# lv_1.net
KiCad netlist of a schematic drawn in Altium Designer
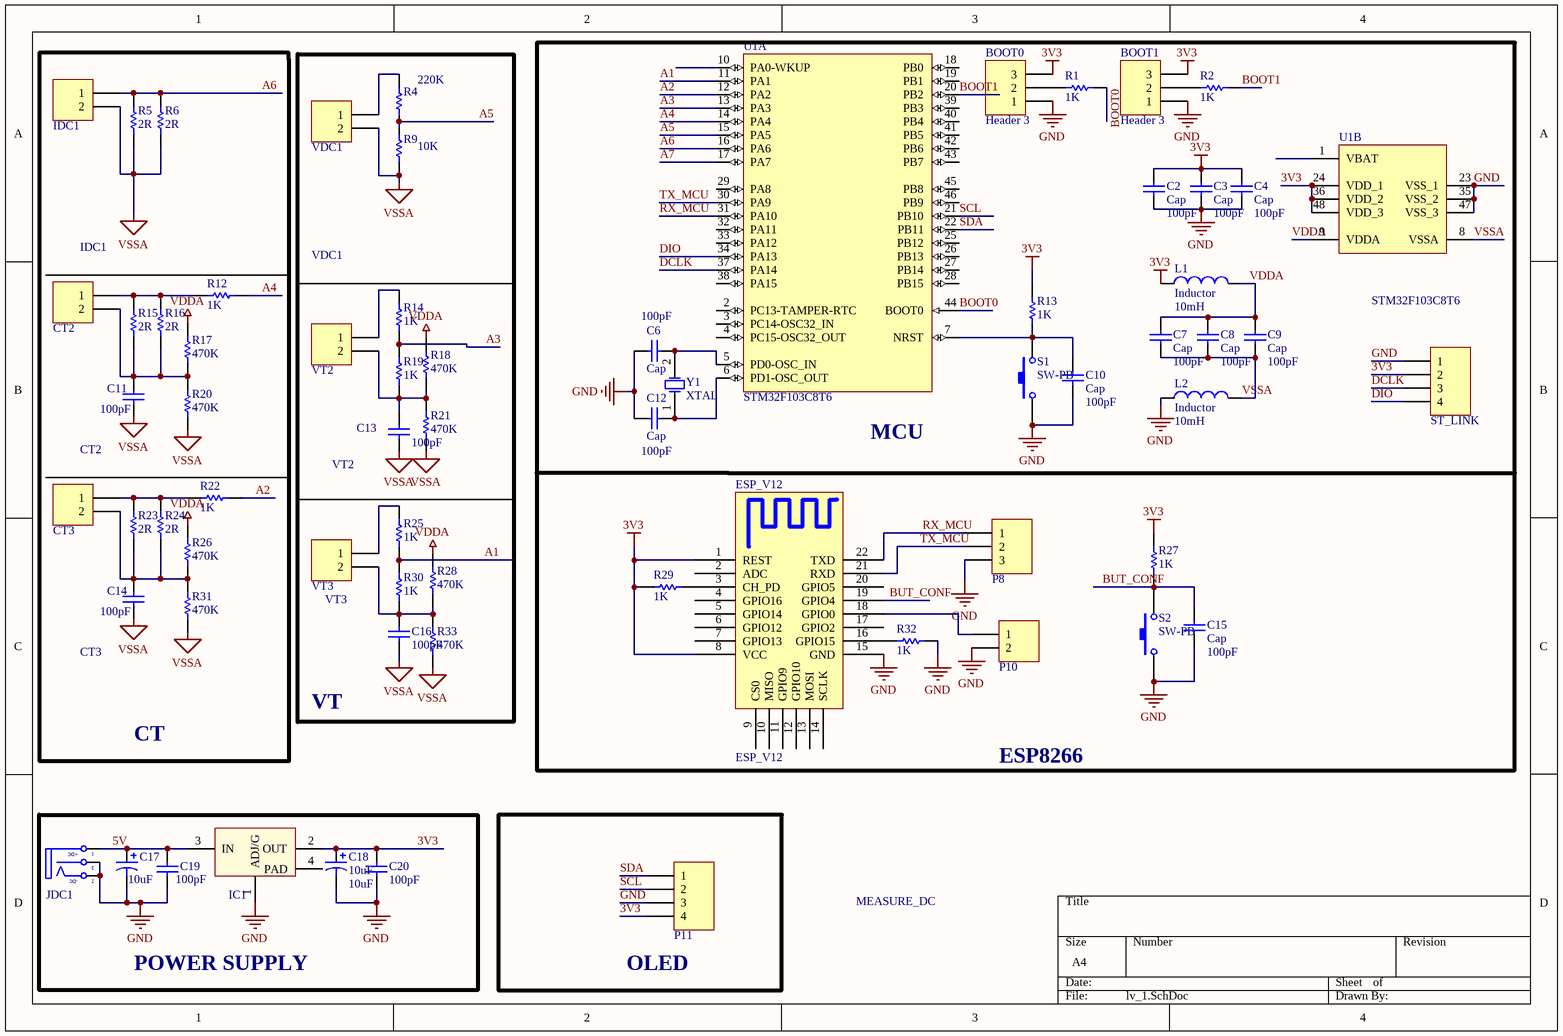
[diagram p0: lv_1.SchDoc]

(export (version "E")
  (design (tool "Eeschema 10.0.6"))
  (components
    (comp (ref "BOOT0")
      (value "Header 3")
      (footprint "JP3")
      (description "Header, 3-Pin")
      (fields (field (name "PUBLISHER") "Altium Limited"))
      (libsource (lib "Miscellaneous Connectors") (part "Header 3"))
    )
    (comp (ref "BOOT1")
      (value "Header 3")
      (footprint "JP3")
      (description "Header, 3-Pin")
      (fields (field (name "PUBLISHER") "Altium Limited"))
      (libsource (lib "Miscellaneous Connectors") (part "Header 3"))
    )
    (comp (ref "C2")
      (value "Cap")
      (footprint "CAP-SM-0603")
      (description "Capacitor")
      (fields (field (name "ALTIUM_VALUE") "100pF") (field (name "PUBLISHER") "Altium Limited"))
      (libsource (lib "Miscellaneous Devices") (part "Cap"))
    )
    (comp (ref "C3")
      (value "Cap")
      (footprint "CAP-SM-0603")
      (description "Capacitor")
      (fields (field (name "ALTIUM_VALUE") "100pF") (field (name "PUBLISHER") "Altium Limited"))
      (libsource (lib "Miscellaneous Devices") (part "Cap"))
    )
    (comp (ref "C4")
      (value "Cap")
      (footprint "CAP-SM-0603")
      (description "Capacitor")
      (fields (field (name "ALTIUM_VALUE") "100pF") (field (name "PUBLISHER") "Altium Limited"))
      (libsource (lib "Miscellaneous Devices") (part "Cap"))
    )
    (comp (ref "C6")
      (value "Cap")
      (footprint "CAP-SM-0603")
      (description "Capacitor")
      (fields (field (name "ALTIUM_VALUE") "100pF") (field (name "PUBLISHER") "Altium Limited"))
      (libsource (lib "Miscellaneous Devices") (part "Cap"))
    )
    (comp (ref "C7")
      (value "Cap")
      (footprint "CAP-SM-0603")
      (description "Capacitor")
      (fields (field (name "ALTIUM_VALUE") "100pF") (field (name "PUBLISHER") "Altium Limited"))
      (libsource (lib "Miscellaneous Devices") (part "Cap"))
    )
    (comp (ref "C8")
      (value "Cap")
      (footprint "CAP-SM-0603")
      (description "Capacitor")
      (fields (field (name "ALTIUM_VALUE") "100pF") (field (name "PUBLISHER") "Altium Limited"))
      (libsource (lib "Miscellaneous Devices") (part "Cap"))
    )
    (comp (ref "C9")
      (value "Cap")
      (footprint "CAP-SM-0603")
      (description "Capacitor")
      (fields (field (name "ALTIUM_VALUE") "100pF") (field (name "PUBLISHER") "Altium Limited"))
      (libsource (lib "Miscellaneous Devices") (part "Cap"))
    )
    (comp (ref "C10")
      (value "Cap")
      (footprint "CAP-SM-0603")
      (description "Capacitor")
      (fields (field (name "ALTIUM_VALUE") "100pF") (field (name "PUBLISHER") "Altium Limited"))
      (libsource (lib "Miscellaneous Devices") (part "Cap"))
    )
    (comp (ref "C11")
      (value "100pF")
      (footprint "CAP-SM-0603")
      (description "Capacitor")
      (fields (field (name "Comment") "Cap Non-Pol SMD"))
      (libsource (lib "PIF_Library") (part "Cap Non-Pol SMD"))
    )
    (comp (ref "C12")
      (value "Cap")
      (footprint "CAP-SM-0603")
      (description "Capacitor")
      (fields (field (name "ALTIUM_VALUE") "100pF") (field (name "PUBLISHER") "Altium Limited"))
      (libsource (lib "Miscellaneous Devices") (part "Cap"))
    )
    (comp (ref "C13")
      (value "100pF")
      (footprint "CAP-SM-0603")
      (description "Capacitor")
      (fields (field (name "Comment") "Cap Non-Pol SMD"))
      (libsource (lib "PIF_Library") (part "Cap Non-Pol SMD"))
    )
    (comp (ref "C14")
      (value "100pF")
      (footprint "CAP-SM-0603")
      (description "Capacitor")
      (fields (field (name "Comment") "Cap Non-Pol SMD"))
      (libsource (lib "PIF_Library") (part "Cap Non-Pol SMD"))
    )
    (comp (ref "C15")
      (value "Cap")
      (footprint "CAP-SM-0603")
      (description "Capacitor")
      (fields (field (name "ALTIUM_VALUE") "100pF") (field (name "PUBLISHER") "Altium Limited"))
      (libsource (lib "Miscellaneous Devices") (part "Cap"))
    )
    (comp (ref "C16")
      (value "100pF")
      (footprint "CAP-SM-0603")
      (description "Capacitor")
      (fields (field (name "Comment") "Cap Non-Pol SMD"))
      (libsource (lib "PIF_Library") (part "Cap Non-Pol SMD"))
    )
    (comp (ref "C17")
      (value "10uF")
      (footprint "CP1/2")
      (description "Polarized Capacitor (Radial)")
      (fields (field (name "PUBLISHER") "Altium Limited"))
      (libsource (lib "Miscellaneous Devices") (part "Cap Pol1"))
    )
    (comp (ref "C18")
      (value "10uF")
      (footprint "CP1/2")
      (description "Polarized Capacitor (Radial)")
      (fields (field (name "ALTIUM_VALUE") "10uF") (field (name "PUBLISHER") "Altium Limited"))
      (libsource (lib "Miscellaneous Devices") (part "Cap Pol1"))
    )
    (comp (ref "C19")
      (value "100pF")
      (footprint "CAP-SM-0603")
      (description "Capacitor")
      (fields (field (name "Comment") "Cap Non-Pol SMD"))
      (libsource (lib "PIF_Library") (part "Cap Non-Pol SMD"))
    )
    (comp (ref "C20")
      (value "100pF")
      (footprint "CAP-SM-0603")
      (description "Capacitor")
      (fields (field (name "Comment") "Cap Non-Pol SMD"))
      (libsource (lib "PIF_Library") (part "Cap Non-Pol SMD"))
    )
    (comp (ref "CT2")
      (value "Domino 2")
      (footprint "DOMINO 2- 5mm")
      (description "Domino, 2-Pin")
      (fields (field (name "PUBLISHER") "Altium Limited"))
      (libsource (lib "PIF_Library") (part "Domino 2"))
    )
    (comp (ref "CT3")
      (value "Domino 2")
      (footprint "DOMINO 2- 5mm")
      (description "Domino, 2-Pin")
      (fields (field (name "PUBLISHER") "Altium Limited"))
      (libsource (lib "PIF_Library") (part "Domino 2"))
    )
    (comp (ref "ESP_V12")
      (value "ESP_V12")
      (footprint "ESP_12_E")
      (libsource (lib "espv12") (part "Component_1"))
    )
    (comp (ref "IC1")
      (value "LM1117")
      (footprint "SOT223-4N")
      (description "Available in 1.8V, 2.5V, 2.85V, 3.3V, 5V, and  Adjustable Versions")
      (libsource (lib "PIF_Library") (part "LM1117"))
    )
    (comp (ref "IDC1")
      (value "Domino 2")
      (footprint "DOMINO 2- 5mm")
      (description "Domino, 2-Pin")
      (fields (field (name "PUBLISHER") "Altium Limited"))
      (libsource (lib "PIF_Library") (part "Domino 2"))
    )
    (comp (ref "JDC1")
      (value "Jack DC")
      (footprint "DC-IN")
      (description "Jack DC input")
      (libsource (lib "PIF_Library") (part "Jack DC"))
    )
    (comp (ref "L1")
      (value "Inductor")
      (footprint "CAP-SM-0603")
      (fields (field (name "ALTIUM_VALUE") "10mH") (field (name "PUBLISHER") "Altium Limited"))
      (libsource (lib "Miscellaneous Devices") (part "Inductor"))
    )
    (comp (ref "L2")
      (value "Inductor")
      (footprint "CAP-SM-0603")
      (fields (field (name "ALTIUM_VALUE") "10mH") (field (name "PUBLISHER") "Altium Limited"))
      (libsource (lib "Miscellaneous Devices") (part "Inductor"))
    )
    (comp (ref "P8")
      (value "Header 3")
      (footprint "JP3")
      (description "Header, 3-Pin")
      (fields (field (name "PUBLISHER") "Altium Limited"))
      (libsource (lib "PIF_Library") (part "Header 3"))
    )
    (comp (ref "P10")
      (value "Header 2")
      (footprint "JP2")
      (description "Header, 2-Pin")
      (fields (field (name "PUBLISHER") "Altium Limited"))
      (libsource (lib "PIF_Library") (part "Header 2"))
    )
    (comp (ref "P11")
      (value "Header 4")
      (footprint "JP4")
      (description "Header, 4-Pin")
      (fields (field (name "PUBLISHER") "Altium Limited"))
      (libsource (lib "PIF_Library") (part "Header 4"))
    )
    (comp (ref "R1")
      (value "1K")
      (footprint "RES-SM-0603")
      (description "Resistor")
      (fields (field (name "Comment") "RESISTOR SMD"))
      (libsource (lib "PIF_Library") (part "RESISTOR SMD"))
    )
    (comp (ref "R2")
      (value "1K")
      (footprint "RES-SM-0603")
      (description "Resistor")
      (fields (field (name "Comment") "RESISTOR SMD"))
      (libsource (lib "PIF_Library") (part "RESISTOR SMD"))
    )
    (comp (ref "R4")
      (value "220K")
      (footprint "RES-SM-0603")
      (description "Resistor")
      (libsource (lib "PIF_Library") (part "RESISTOR SMD"))
    )
    (comp (ref "R5")
      (value "2R")
      (footprint "RES-SM-0603")
      (description "Resistor")
      (fields (field (name "Comment") "RESISTOR SMD"))
      (libsource (lib "PIF_Library") (part "RESISTOR SMD"))
    )
    (comp (ref "R6")
      (value "2R")
      (footprint "RES-SM-0603")
      (description "Resistor")
      (fields (field (name "Comment") "RESISTOR SMD"))
      (libsource (lib "PIF_Library") (part "RESISTOR SMD"))
    )
    (comp (ref "R9")
      (value "10K")
      (footprint "RES-SM-0603")
      (description "Resistor")
      (libsource (lib "PIF_Library") (part "RESISTOR SMD"))
    )
    (comp (ref "R12")
      (value "1K")
      (footprint "RES-SM-0603")
      (description "Resistor")
      (fields (field (name "Comment") "RESISTOR SMD"))
      (libsource (lib "PIF_Library") (part "RESISTOR SMD"))
    )
    (comp (ref "R13")
      (value "1K")
      (footprint "RES-SM-0603")
      (description "Resistor")
      (fields (field (name "Comment") "RESISTOR SMD"))
      (libsource (lib "PIF_Library") (part "RESISTOR SMD"))
    )
    (comp (ref "R14")
      (value "1K")
      (footprint "RES-SM-0603")
      (description "Resistor")
      (fields (field (name "Comment") "RESISTOR SMD"))
      (libsource (lib "PIF_Library") (part "RESISTOR SMD"))
    )
    (comp (ref "R15")
      (value "2R")
      (footprint "RES-SM-0603")
      (description "Resistor")
      (fields (field (name "Comment") "RESISTOR SMD"))
      (libsource (lib "PIF_Library") (part "RESISTOR SMD"))
    )
    (comp (ref "R16")
      (value "2R")
      (footprint "RES-SM-0603")
      (description "Resistor")
      (fields (field (name "Comment") "RESISTOR SMD"))
      (libsource (lib "PIF_Library") (part "RESISTOR SMD"))
    )
    (comp (ref "R17")
      (value "470K")
      (footprint "RES-SM-0603")
      (description "Resistor")
      (fields (field (name "Comment") "RESISTOR SMD"))
      (libsource (lib "PIF_Library") (part "RESISTOR SMD"))
    )
    (comp (ref "R18")
      (value "470K")
      (footprint "RES-SM-0603")
      (description "Resistor")
      (fields (field (name "Comment") "RESISTOR SMD"))
      (libsource (lib "PIF_Library") (part "RESISTOR SMD"))
    )
    (comp (ref "R19")
      (value "1K")
      (footprint "RES-SM-0603")
      (description "Resistor")
      (fields (field (name "Comment") "RESISTOR SMD"))
      (libsource (lib "PIF_Library") (part "RESISTOR SMD"))
    )
    (comp (ref "R20")
      (value "470K")
      (footprint "RES-SM-0603")
      (description "Resistor")
      (fields (field (name "Comment") "RESISTOR SMD"))
      (libsource (lib "PIF_Library") (part "RESISTOR SMD"))
    )
    (comp (ref "R21")
      (value "470K")
      (footprint "RES-SM-0603")
      (description "Resistor")
      (fields (field (name "Comment") "RESISTOR SMD"))
      (libsource (lib "PIF_Library") (part "RESISTOR SMD"))
    )
    (comp (ref "R22")
      (value "1K")
      (footprint "RES-SM-0603")
      (description "Resistor")
      (fields (field (name "Comment") "RESISTOR SMD"))
      (libsource (lib "PIF_Library") (part "RESISTOR SMD"))
    )
    (comp (ref "R23")
      (value "2R")
      (footprint "RES-SM-0603")
      (description "Resistor")
      (fields (field (name "Comment") "RESISTOR SMD"))
      (libsource (lib "PIF_Library") (part "RESISTOR SMD"))
    )
    (comp (ref "R24")
      (value "2R")
      (footprint "RES-SM-0603")
      (description "Resistor")
      (fields (field (name "Comment") "RESISTOR SMD"))
      (libsource (lib "PIF_Library") (part "RESISTOR SMD"))
    )
    (comp (ref "R25")
      (value "1K")
      (footprint "RES-SM-0603")
      (description "Resistor")
      (fields (field (name "Comment") "RESISTOR SMD"))
      (libsource (lib "PIF_Library") (part "RESISTOR SMD"))
    )
    (comp (ref "R26")
      (value "470K")
      (footprint "RES-SM-0603")
      (description "Resistor")
      (fields (field (name "Comment") "RESISTOR SMD"))
      (libsource (lib "PIF_Library") (part "RESISTOR SMD"))
    )
    (comp (ref "R27")
      (value "1K")
      (footprint "RES-SM-0603")
      (description "Resistor")
      (fields (field (name "Comment") "RESISTOR SMD"))
      (libsource (lib "PIF_Library") (part "RESISTOR SMD"))
    )
    (comp (ref "R28")
      (value "470K")
      (footprint "RES-SM-0603")
      (description "Resistor")
      (fields (field (name "Comment") "RESISTOR SMD"))
      (libsource (lib "PIF_Library") (part "RESISTOR SMD"))
    )
    (comp (ref "R29")
      (value "1K")
      (footprint "RES-SM-0603")
      (description "Resistor")
      (fields (field (name "Comment") "RESISTOR SMD"))
      (libsource (lib "PIF_Library") (part "RESISTOR SMD"))
    )
    (comp (ref "R30")
      (value "1K")
      (footprint "RES-SM-0603")
      (description "Resistor")
      (fields (field (name "Comment") "RESISTOR SMD"))
      (libsource (lib "PIF_Library") (part "RESISTOR SMD"))
    )
    (comp (ref "R31")
      (value "470K")
      (footprint "RES-SM-0603")
      (description "Resistor")
      (fields (field (name "Comment") "RESISTOR SMD"))
      (libsource (lib "PIF_Library") (part "RESISTOR SMD"))
    )
    (comp (ref "R32")
      (value "1K")
      (footprint "RES-SM-0603")
      (description "Resistor")
      (fields (field (name "Comment") "RESISTOR SMD"))
      (libsource (lib "PIF_Library") (part "RESISTOR SMD"))
    )
    (comp (ref "R33")
      (value "470K")
      (footprint "RES-SM-0603")
      (description "Resistor")
      (fields (field (name "Comment") "RESISTOR SMD"))
      (libsource (lib "PIF_Library") (part "RESISTOR SMD"))
    )
    (comp (ref "S1")
      (value "SW-PB")
      (footprint "Tact SW 4 pin")
      (description "Switch")
      (fields (field (name "PUBLISHER") "Altium Limited"))
      (libsource (lib "Miscellaneous Devices") (part "SW-PB"))
    )
    (comp (ref "S2")
      (value "SW-PB")
      (footprint "Tact SW 4 pin")
      (description "Switch")
      (fields (field (name "PUBLISHER") "Altium Limited"))
      (libsource (lib "Miscellaneous Devices") (part "SW-PB"))
    )
    (comp (ref "ST_LINK")
      (value "Header 4")
      (footprint "JP4")
      (description "Header, 4-Pin")
      (fields (field (name "PUBLISHER") "Altium Limited"))
      (libsource (lib "PIF_Schematic_Lib") (part "Header 4"))
    )
    (comp (ref "U1")
      (value "STM32F103C8T6")
      (footprint "STM-LQFP48_L")
      (libsource (lib "STMicroelectronics STM32 F1") (part "STM32F103C8T6"))
    )
    (comp (ref "VDC1")
      (value "Domino 2")
      (footprint "DOMINO 2- 5mm")
      (description "Domino, 2-Pin")
      (fields (field (name "PUBLISHER") "Altium Limited"))
      (libsource (lib "PIF_Library") (part "Domino 2"))
    )
    (comp (ref "VT2")
      (value "Domino 2")
      (footprint "DOMINO 2- 5mm")
      (description "Domino, 2-Pin")
      (fields (field (name "PUBLISHER") "Altium Limited"))
      (libsource (lib "PIF_Library") (part "Domino 2"))
    )
    (comp (ref "VT3")
      (value "Domino 2")
      (footprint "DOMINO 2- 5mm")
      (description "Domino, 2-Pin")
      (fields (field (name "PUBLISHER") "Altium Limited"))
      (libsource (lib "PIF_Library") (part "Domino 2"))
    )
    (comp (ref "Y1")
      (value "XTAL")
      (footprint "XT2")
      (description "Crystal Oscillator")
      (fields (field (name "PUBLISHER") "Altium Limited"))
      (libsource (lib "Miscellaneous Devices") (part "XTAL"))
    )
  )
  (nets
    (net (code "1") (name "/5V") (class "Default")
      (node (ref "C17") (pin "1") (pinfunction "1_1") (pintype "passive"))
      (node (ref "C19") (pin "2") (pinfunction "2_2") (pintype "passive"))
      (node (ref "IC1") (pin "3") (pinfunction "IN_3") (pintype "passive"))
      (node (ref "JDC1") (pin "1") (pinfunction "T_1") (pintype "passive"))
    )
    (net (code "2") (name "/A1") (class "Default")
      (node (ref "R25") (pin "1") (pinfunction "1_1") (pintype "passive"))
      (node (ref "R30") (pin "2") (pinfunction "2_2") (pintype "passive"))
      (node (ref "U1") (pin "11") (pinfunction "PA1_11") (pintype "bidirectional"))
    )
    (net (code "3") (name "/A2") (class "Default")
      (node (ref "R22") (pin "1") (pinfunction "1_1") (pintype "passive"))
      (node (ref "U1") (pin "12") (pinfunction "PA2_12") (pintype "bidirectional"))
    )
    (net (code "4") (name "/A3") (class "Default")
      (node (ref "R14") (pin "1") (pinfunction "1_1") (pintype "passive"))
      (node (ref "R19") (pin "2") (pinfunction "2_2") (pintype "passive"))
      (node (ref "U1") (pin "13") (pinfunction "PA3_13") (pintype "bidirectional"))
    )
    (net (code "5") (name "/A4") (class "Default")
      (node (ref "R12") (pin "1") (pinfunction "1_1") (pintype "passive"))
      (node (ref "U1") (pin "14") (pinfunction "PA4_14") (pintype "bidirectional"))
    )
    (net (code "6") (name "/A5") (class "Default")
      (node (ref "R4") (pin "1") (pinfunction "1_1") (pintype "passive"))
      (node (ref "R9") (pin "2") (pinfunction "2_2") (pintype "passive"))
      (node (ref "U1") (pin "15") (pinfunction "PA5_15") (pintype "bidirectional"))
    )
    (net (code "7") (name "/A6") (class "Default")
      (node (ref "IDC1") (pin "1") (pinfunction "1_1") (pintype "passive"))
      (node (ref "R5") (pin "2") (pinfunction "2_2") (pintype "passive"))
      (node (ref "R6") (pin "2") (pinfunction "2_2") (pintype "passive"))
      (node (ref "U1") (pin "16") (pinfunction "PA6_16") (pintype "bidirectional"))
    )
    (net (code "8") (name "/A7") (class "Default")
      (node (ref "U1") (pin "17") (pinfunction "PA7_17") (pintype "bidirectional"))
    )
    (net (code "9") (name "/BOOT0") (class "Default")
      (node (ref "R1") (pin "1") (pinfunction "1_1") (pintype "passive"))
      (node (ref "U1") (pin "44") (pinfunction "BOOT0_44") (pintype "input"))
    )
    (net (code "10") (name "/BOOT1") (class "Default")
      (node (ref "R2") (pin "1") (pinfunction "1_1") (pintype "passive"))
      (node (ref "U1") (pin "20") (pinfunction "PB2_20") (pintype "bidirectional"))
    )
    (net (code "11") (name "/BUT_CONF") (class "Default")
      (node (ref "C15") (pin "2") (pinfunction "2_2") (pintype "passive"))
      (node (ref "ESP_V12") (pin "19") (pinfunction "GPIO4_19") (pintype "passive"))
      (node (ref "R27") (pin "2") (pinfunction "2_2") (pintype "passive"))
      (node (ref "S2") (pin "2") (pinfunction "2_2") (pintype "passive"))
    )
    (net (code "12") (name "/DCLK") (class "Default")
      (node (ref "ST_LINK") (pin "3") (pinfunction "3_3") (pintype "passive"))
      (node (ref "U1") (pin "37") (pinfunction "PA14_37") (pintype "bidirectional"))
    )
    (net (code "13") (name "/DIO") (class "Default")
      (node (ref "ST_LINK") (pin "4") (pinfunction "4_4") (pintype "passive"))
      (node (ref "U1") (pin "34") (pinfunction "PA13_34") (pintype "bidirectional"))
    )
    (net (code "14") (name "/RX_MCU") (class "Default")
      (node (ref "ESP_V12") (pin "22") (pinfunction "TXD_22") (pintype "passive"))
      (node (ref "P8") (pin "1") (pinfunction "1_1") (pintype "passive"))
      (node (ref "U1") (pin "31") (pinfunction "PA10_31") (pintype "bidirectional"))
    )
    (net (code "15") (name "/SCL") (class "Default")
      (node (ref "P11") (pin "2") (pinfunction "2_2") (pintype "passive"))
      (node (ref "U1") (pin "21") (pinfunction "PB10_21") (pintype "bidirectional"))
    )
    (net (code "16") (name "/SDA") (class "Default")
      (node (ref "P11") (pin "1") (pinfunction "1_1") (pintype "passive"))
      (node (ref "U1") (pin "22") (pinfunction "PB11_22") (pintype "bidirectional"))
    )
    (net (code "17") (name "/TX_MCU") (class "Default")
      (node (ref "ESP_V12") (pin "21") (pinfunction "RXD_21") (pintype "passive"))
      (node (ref "P8") (pin "2") (pinfunction "2_2") (pintype "passive"))
      (node (ref "U1") (pin "30") (pinfunction "PA9_30") (pintype "bidirectional"))
    )
    (net (code "18") (name "3V3") (class "Default")
      (node (ref "BOOT0") (pin "3") (pinfunction "3_3") (pintype "passive"))
      (node (ref "BOOT1") (pin "3") (pinfunction "3_3") (pintype "passive"))
      (node (ref "C18") (pin "1") (pinfunction "1_1") (pintype "passive"))
      (node (ref "C2") (pin "2") (pinfunction "2_2") (pintype "passive"))
      (node (ref "C20") (pin "2") (pinfunction "2_2") (pintype "passive"))
      (node (ref "C3") (pin "2") (pinfunction "2_2") (pintype "passive"))
      (node (ref "C4") (pin "2") (pinfunction "2_2") (pintype "passive"))
      (node (ref "ESP_V12") (pin "1") (pinfunction "REST_1") (pintype "passive"))
      (node (ref "ESP_V12") (pin "8") (pinfunction "VCC_8") (pintype "passive"))
      (node (ref "IC1") (pin "2") (pinfunction "OUT_2") (pintype "passive"))
      (node (ref "L1") (pin "1") (pinfunction "1_1") (pintype "passive"))
      (node (ref "P11") (pin "4") (pinfunction "4_4") (pintype "passive"))
      (node (ref "R13") (pin "1") (pinfunction "1_1") (pintype "passive"))
      (node (ref "R27") (pin "1") (pinfunction "1_1") (pintype "passive"))
      (node (ref "R29") (pin "1") (pinfunction "1_1") (pintype "passive"))
      (node (ref "ST_LINK") (pin "2") (pinfunction "2_2") (pintype "passive"))
      (node (ref "U1") (pin "24") (pinfunction "VDD_1_24") (pintype "power_in"))
      (node (ref "U1") (pin "36") (pinfunction "VDD_2_36") (pintype "power_in"))
      (node (ref "U1") (pin "48") (pinfunction "VDD_3_48") (pintype "power_in"))
    )
    (net (code "19") (name "GND") (class "Default")
      (node (ref "BOOT0") (pin "1") (pinfunction "1_1") (pintype "passive"))
      (node (ref "BOOT1") (pin "1") (pinfunction "1_1") (pintype "passive"))
      (node (ref "C10") (pin "1") (pinfunction "1_1") (pintype "passive"))
      (node (ref "C12") (pin "1") (pinfunction "1_1") (pintype "passive"))
      (node (ref "C15") (pin "1") (pinfunction "1_1") (pintype "passive"))
      (node (ref "C17") (pin "2") (pinfunction "2_2") (pintype "passive"))
      (node (ref "C18") (pin "2") (pinfunction "2_2") (pintype "passive"))
      (node (ref "C19") (pin "1") (pinfunction "1_1") (pintype "passive"))
      (node (ref "C2") (pin "1") (pinfunction "1_1") (pintype "passive"))
      (node (ref "C20") (pin "1") (pinfunction "1_1") (pintype "passive"))
      (node (ref "C3") (pin "1") (pinfunction "1_1") (pintype "passive"))
      (node (ref "C4") (pin "1") (pinfunction "1_1") (pintype "passive"))
      (node (ref "C6") (pin "1") (pinfunction "1_1") (pintype "passive"))
      (node (ref "ESP_V12") (pin "15") (pinfunction "GND_15") (pintype "passive"))
      (node (ref "IC1") (pin "1") (pinfunction "ADJ/G_1") (pintype "passive"))
      (node (ref "JDC1") (pin "2") (pinfunction "TN_2") (pintype "passive"))
      (node (ref "JDC1") (pin "3") (pinfunction "S_3") (pintype "power_in"))
      (node (ref "L2") (pin "1") (pinfunction "1_1") (pintype "passive"))
      (node (ref "P10") (pin "2") (pinfunction "2_2") (pintype "passive"))
      (node (ref "P11") (pin "3") (pinfunction "3_3") (pintype "passive"))
      (node (ref "P8") (pin "3") (pinfunction "3_3") (pintype "passive"))
      (node (ref "R32") (pin "2") (pinfunction "2_2") (pintype "passive"))
      (node (ref "S1") (pin "1") (pinfunction "1_1") (pintype "passive"))
      (node (ref "S2") (pin "1") (pinfunction "1_1") (pintype "passive"))
      (node (ref "ST_LINK") (pin "1") (pinfunction "1_1") (pintype "passive"))
      (node (ref "U1") (pin "23") (pinfunction "VSS_1_23") (pintype "power_in"))
      (node (ref "U1") (pin "35") (pinfunction "VSS_2_35") (pintype "power_in"))
      (node (ref "U1") (pin "47") (pinfunction "VSS_3_47") (pintype "power_in"))
    )
    (net (code "20") (name "Net-(BOOT0-Pad2)") (class "Default")
      (node (ref "BOOT0") (pin "2") (pinfunction "2_2") (pintype "passive"))
      (node (ref "R1") (pin "2") (pinfunction "2_2") (pintype "passive"))
    )
    (net (code "21") (name "Net-(BOOT1-Pad2)") (class "Default")
      (node (ref "BOOT1") (pin "2") (pinfunction "2_2") (pintype "passive"))
      (node (ref "R2") (pin "2") (pinfunction "2_2") (pintype "passive"))
    )
    (net (code "22") (name "Net-(C11-Pad2)") (class "Default")
      (node (ref "C11") (pin "2") (pinfunction "2_2") (pintype "passive"))
      (node (ref "CT2") (pin "2") (pinfunction "2_2") (pintype "passive"))
      (node (ref "R15") (pin "1") (pinfunction "1_1") (pintype "passive"))
      (node (ref "R16") (pin "1") (pinfunction "1_1") (pintype "passive"))
      (node (ref "R17") (pin "1") (pinfunction "1_1") (pintype "passive"))
      (node (ref "R20") (pin "2") (pinfunction "2_2") (pintype "passive"))
    )
    (net (code "23") (name "Net-(C13-Pad2)") (class "Default")
      (node (ref "C13") (pin "2") (pinfunction "2_2") (pintype "passive"))
      (node (ref "R18") (pin "1") (pinfunction "1_1") (pintype "passive"))
      (node (ref "R19") (pin "1") (pinfunction "1_1") (pintype "passive"))
      (node (ref "R21") (pin "2") (pinfunction "2_2") (pintype "passive"))
      (node (ref "VT2") (pin "2") (pinfunction "2_2") (pintype "passive"))
    )
    (net (code "24") (name "Net-(C14-Pad2)") (class "Default")
      (node (ref "C14") (pin "2") (pinfunction "2_2") (pintype "passive"))
      (node (ref "CT3") (pin "2") (pinfunction "2_2") (pintype "passive"))
      (node (ref "R23") (pin "1") (pinfunction "1_1") (pintype "passive"))
      (node (ref "R24") (pin "1") (pinfunction "1_1") (pintype "passive"))
      (node (ref "R26") (pin "1") (pinfunction "1_1") (pintype "passive"))
      (node (ref "R31") (pin "2") (pinfunction "2_2") (pintype "passive"))
    )
    (net (code "25") (name "Net-(C16-Pad2)") (class "Default")
      (node (ref "C16") (pin "2") (pinfunction "2_2") (pintype "passive"))
      (node (ref "R28") (pin "1") (pinfunction "1_1") (pintype "passive"))
      (node (ref "R30") (pin "1") (pinfunction "1_1") (pintype "passive"))
      (node (ref "R33") (pin "2") (pinfunction "2_2") (pintype "passive"))
      (node (ref "VT3") (pin "2") (pinfunction "2_2") (pintype "passive"))
    )
    (net (code "26") (name "Net-(CT2-Pad1)") (class "Default")
      (node (ref "CT2") (pin "1") (pinfunction "1_1") (pintype "passive"))
      (node (ref "R12") (pin "2") (pinfunction "2_2") (pintype "passive"))
      (node (ref "R15") (pin "2") (pinfunction "2_2") (pintype "passive"))
      (node (ref "R16") (pin "2") (pinfunction "2_2") (pintype "passive"))
    )
    (net (code "27") (name "Net-(CT3-Pad1)") (class "Default")
      (node (ref "CT3") (pin "1") (pinfunction "1_1") (pintype "passive"))
      (node (ref "R22") (pin "2") (pinfunction "2_2") (pintype "passive"))
      (node (ref "R23") (pin "2") (pinfunction "2_2") (pintype "passive"))
      (node (ref "R24") (pin "2") (pinfunction "2_2") (pintype "passive"))
    )
    (net (code "28") (name "Net-(ESP_V12-CH_PD)") (class "Default")
      (node (ref "ESP_V12") (pin "3") (pinfunction "CH_PD_3") (pintype "passive"))
      (node (ref "R29") (pin "2") (pinfunction "2_2") (pintype "passive"))
    )
    (net (code "29") (name "Net-(ESP_V12-GPIO0)") (class "Default")
      (node (ref "ESP_V12") (pin "18") (pinfunction "GPIO0_18") (pintype "passive"))
      (node (ref "P10") (pin "1") (pinfunction "1_1") (pintype "passive"))
    )
    (net (code "30") (name "Net-(ESP_V12-GPIO15)") (class "Default")
      (node (ref "ESP_V12") (pin "16") (pinfunction "GPIO15_16") (pintype "passive"))
      (node (ref "R32") (pin "1") (pinfunction "1_1") (pintype "passive"))
    )
    (net (code "31") (name "Net-(R4-Pad2)") (class "Default")
      (node (ref "R4") (pin "2") (pinfunction "2_2") (pintype "passive"))
      (node (ref "VDC1") (pin "1") (pinfunction "1_1") (pintype "passive"))
    )
    (net (code "32") (name "Net-(R14-Pad2)") (class "Default")
      (node (ref "R14") (pin "2") (pinfunction "2_2") (pintype "passive"))
      (node (ref "VT2") (pin "1") (pinfunction "1_1") (pintype "passive"))
    )
    (net (code "33") (name "Net-(R25-Pad2)") (class "Default")
      (node (ref "R25") (pin "2") (pinfunction "2_2") (pintype "passive"))
      (node (ref "VT3") (pin "1") (pinfunction "1_1") (pintype "passive"))
    )
    (net (code "34") (name "Net-(U1A-NRST)") (class "Default")
      (node (ref "C10") (pin "2") (pinfunction "2_2") (pintype "passive"))
      (node (ref "R13") (pin "2") (pinfunction "2_2") (pintype "passive"))
      (node (ref "S1") (pin "2") (pinfunction "2_2") (pintype "passive"))
      (node (ref "U1") (pin "7") (pinfunction "NRST_7") (pintype "bidirectional"))
    )
    (net (code "35") (name "Net-(U1A-PD0-OSC_IN)") (class "Default")
      (node (ref "C6") (pin "2") (pinfunction "2_2") (pintype "passive"))
      (node (ref "U1") (pin "5") (pinfunction "PD0-OSC_IN_5") (pintype "bidirectional"))
      (node (ref "Y1") (pin "2") (pinfunction "OSC2_2") (pintype "passive"))
    )
    (net (code "36") (name "Net-(U1A-PD1-OSC_OUT)") (class "Default")
      (node (ref "C12") (pin "2") (pinfunction "2_2") (pintype "passive"))
      (node (ref "U1") (pin "6") (pinfunction "PD1-OSC_OUT_6") (pintype "bidirectional"))
      (node (ref "Y1") (pin "1") (pinfunction "OSC1_1") (pintype "passive"))
    )
    (net (code "37") (name "VDDA") (class "Default")
      (node (ref "C7") (pin "2") (pinfunction "2_2") (pintype "passive"))
      (node (ref "C8") (pin "2") (pinfunction "2_2") (pintype "passive"))
      (node (ref "C9") (pin "2") (pinfunction "2_2") (pintype "passive"))
      (node (ref "L1") (pin "2") (pinfunction "2_2") (pintype "passive"))
      (node (ref "R17") (pin "2") (pinfunction "2_2") (pintype "passive"))
      (node (ref "R18") (pin "2") (pinfunction "2_2") (pintype "passive"))
      (node (ref "R26") (pin "2") (pinfunction "2_2") (pintype "passive"))
      (node (ref "R28") (pin "2") (pinfunction "2_2") (pintype "passive"))
      (node (ref "U1") (pin "9") (pinfunction "VDDA_9") (pintype "power_in"))
    )
    (net (code "38") (name "VSSA") (class "Default")
      (node (ref "C11") (pin "1") (pinfunction "1_1") (pintype "passive"))
      (node (ref "C13") (pin "1") (pinfunction "1_1") (pintype "passive"))
      (node (ref "C14") (pin "1") (pinfunction "1_1") (pintype "passive"))
      (node (ref "C16") (pin "1") (pinfunction "1_1") (pintype "passive"))
      (node (ref "C7") (pin "1") (pinfunction "1_1") (pintype "passive"))
      (node (ref "C8") (pin "1") (pinfunction "1_1") (pintype "passive"))
      (node (ref "C9") (pin "1") (pinfunction "1_1") (pintype "passive"))
      (node (ref "IDC1") (pin "2") (pinfunction "2_2") (pintype "passive"))
      (node (ref "L2") (pin "2") (pinfunction "2_2") (pintype "passive"))
      (node (ref "R20") (pin "1") (pinfunction "1_1") (pintype "passive"))
      (node (ref "R21") (pin "1") (pinfunction "1_1") (pintype "passive"))
      (node (ref "R31") (pin "1") (pinfunction "1_1") (pintype "passive"))
      (node (ref "R33") (pin "1") (pinfunction "1_1") (pintype "passive"))
      (node (ref "R5") (pin "1") (pinfunction "1_1") (pintype "passive"))
      (node (ref "R6") (pin "1") (pinfunction "1_1") (pintype "passive"))
      (node (ref "R9") (pin "1") (pinfunction "1_1") (pintype "passive"))
      (node (ref "U1") (pin "8") (pinfunction "VSSA_8") (pintype "power_in"))
      (node (ref "VDC1") (pin "2") (pinfunction "2_2") (pintype "passive"))
    )
    (net (code "39") (name "unconnected-(ESP_V12-ADC-Pad2)") (class "Default")
      (node (ref "ESP_V12") (pin "2") (pinfunction "ADC_2") (pintype "passive"))
    )
    (net (code "40") (name "unconnected-(ESP_V12-CS0-Pad9)") (class "Default")
      (node (ref "ESP_V12") (pin "9") (pinfunction "CS0_9") (pintype "passive"))
    )
    (net (code "41") (name "unconnected-(ESP_V12-GPIO2-Pad17)") (class "Default")
      (node (ref "ESP_V12") (pin "17") (pinfunction "GPIO2_17") (pintype "passive"))
    )
    (net (code "42") (name "unconnected-(ESP_V12-GPIO5-Pad20)") (class "Default")
      (node (ref "ESP_V12") (pin "20") (pinfunction "GPIO5_20") (pintype "passive"))
    )
    (net (code "43") (name "unconnected-(ESP_V12-GPIO9-Pad11)") (class "Default")
      (node (ref "ESP_V12") (pin "11") (pinfunction "GPIO9_11") (pintype "passive"))
    )
    (net (code "44") (name "unconnected-(ESP_V12-GPIO10-Pad12)") (class "Default")
      (node (ref "ESP_V12") (pin "12") (pinfunction "GPIO10_12") (pintype "passive"))
    )
    (net (code "45") (name "unconnected-(ESP_V12-GPIO12-Pad6)") (class "Default")
      (node (ref "ESP_V12") (pin "6") (pinfunction "GPIO12_6") (pintype "passive"))
    )
    (net (code "46") (name "unconnected-(ESP_V12-GPIO13-Pad7)") (class "Default")
      (node (ref "ESP_V12") (pin "7") (pinfunction "GPIO13_7") (pintype "passive"))
    )
    (net (code "47") (name "unconnected-(ESP_V12-GPIO14-Pad5)") (class "Default")
      (node (ref "ESP_V12") (pin "5") (pinfunction "GPIO14_5") (pintype "passive"))
    )
    (net (code "48") (name "unconnected-(ESP_V12-GPIO16-Pad4)") (class "Default")
      (node (ref "ESP_V12") (pin "4") (pinfunction "GPIO16_4") (pintype "passive"))
    )
    (net (code "49") (name "unconnected-(ESP_V12-MISO-Pad10)") (class "Default")
      (node (ref "ESP_V12") (pin "10") (pinfunction "MISO_10") (pintype "passive"))
    )
    (net (code "50") (name "unconnected-(ESP_V12-MOSI-Pad13)") (class "Default")
      (node (ref "ESP_V12") (pin "13") (pinfunction "MOSI_13") (pintype "passive"))
    )
    (net (code "51") (name "unconnected-(ESP_V12-SCLK-Pad14)") (class "Default")
      (node (ref "ESP_V12") (pin "14") (pinfunction "SCLK_14") (pintype "passive"))
    )
    (net (code "52") (name "unconnected-(IC1-PAD-Pad4)") (class "Default")
      (node (ref "IC1") (pin "4") (pinfunction "PAD_4") (pintype "passive"))
    )
    (net (code "53") (name "unconnected-(U1A-PA0-WKUP-Pad10)") (class "Default")
      (node (ref "U1") (pin "10") (pinfunction "PA0-WKUP_10") (pintype "bidirectional"))
    )
    (net (code "54") (name "unconnected-(U1A-PA8-Pad29)") (class "Default")
      (node (ref "U1") (pin "29") (pinfunction "PA8_29") (pintype "bidirectional"))
    )
    (net (code "55") (name "unconnected-(U1A-PA11-Pad32)") (class "Default")
      (node (ref "U1") (pin "32") (pinfunction "PA11_32") (pintype "bidirectional"))
    )
    (net (code "56") (name "unconnected-(U1A-PA12-Pad33)") (class "Default")
      (node (ref "U1") (pin "33") (pinfunction "PA12_33") (pintype "bidirectional"))
    )
    (net (code "57") (name "unconnected-(U1A-PA15-Pad38)") (class "Default")
      (node (ref "U1") (pin "38") (pinfunction "PA15_38") (pintype "bidirectional"))
    )
    (net (code "58") (name "unconnected-(U1A-PB0-Pad18)") (class "Default")
      (node (ref "U1") (pin "18") (pinfunction "PB0_18") (pintype "bidirectional"))
    )
    (net (code "59") (name "unconnected-(U1A-PB1-Pad19)") (class "Default")
      (node (ref "U1") (pin "19") (pinfunction "PB1_19") (pintype "bidirectional"))
    )
    (net (code "60") (name "unconnected-(U1A-PB3-Pad39)") (class "Default")
      (node (ref "U1") (pin "39") (pinfunction "PB3_39") (pintype "bidirectional"))
    )
    (net (code "61") (name "unconnected-(U1A-PB4-Pad40)") (class "Default")
      (node (ref "U1") (pin "40") (pinfunction "PB4_40") (pintype "bidirectional"))
    )
    (net (code "62") (name "unconnected-(U1A-PB5-Pad41)") (class "Default")
      (node (ref "U1") (pin "41") (pinfunction "PB5_41") (pintype "bidirectional"))
    )
    (net (code "63") (name "unconnected-(U1A-PB6-Pad42)") (class "Default")
      (node (ref "U1") (pin "42") (pinfunction "PB6_42") (pintype "bidirectional"))
    )
    (net (code "64") (name "unconnected-(U1A-PB7-Pad43)") (class "Default")
      (node (ref "U1") (pin "43") (pinfunction "PB7_43") (pintype "bidirectional"))
    )
    (net (code "65") (name "unconnected-(U1A-PB8-Pad45)") (class "Default")
      (node (ref "U1") (pin "45") (pinfunction "PB8_45") (pintype "bidirectional"))
    )
    (net (code "66") (name "unconnected-(U1A-PB9-Pad46)") (class "Default")
      (node (ref "U1") (pin "46") (pinfunction "PB9_46") (pintype "bidirectional"))
    )
    (net (code "67") (name "unconnected-(U1A-PB12-Pad25)") (class "Default")
      (node (ref "U1") (pin "25") (pinfunction "PB12_25") (pintype "bidirectional"))
    )
    (net (code "68") (name "unconnected-(U1A-PB13-Pad26)") (class "Default")
      (node (ref "U1") (pin "26") (pinfunction "PB13_26") (pintype "bidirectional"))
    )
    (net (code "69") (name "unconnected-(U1A-PB14-Pad27)") (class "Default")
      (node (ref "U1") (pin "27") (pinfunction "PB14_27") (pintype "bidirectional"))
    )
    (net (code "70") (name "unconnected-(U1A-PB15-Pad28)") (class "Default")
      (node (ref "U1") (pin "28") (pinfunction "PB15_28") (pintype "bidirectional"))
    )
    (net (code "71") (name "unconnected-(U1A-PC13-TAMPER-RTC-Pad2)") (class "Default")
      (node (ref "U1") (pin "2") (pinfunction "PC13-TAMPER-RTC_2") (pintype "bidirectional"))
    )
    (net (code "72") (name "unconnected-(U1A-PC14-OSC32_IN-Pad3)") (class "Default")
      (node (ref "U1") (pin "3") (pinfunction "PC14-OSC32_IN_3") (pintype "bidirectional"))
    )
    (net (code "73") (name "unconnected-(U1A-PC15-OSC32_OUT-Pad4)") (class "Default")
      (node (ref "U1") (pin "4") (pinfunction "PC15-OSC32_OUT_4") (pintype "bidirectional"))
    )
    (net (code "74") (name "unconnected-(U1B-VBAT-Pad1)") (class "Default")
      (node (ref "U1") (pin "1") (pinfunction "VBAT_1") (pintype "power_in"))
    )
  )
)
